# SCH_Syntheseproject_proof_of_concept_com.net
KiCad netlist of a schematic drawn in EasyEDA
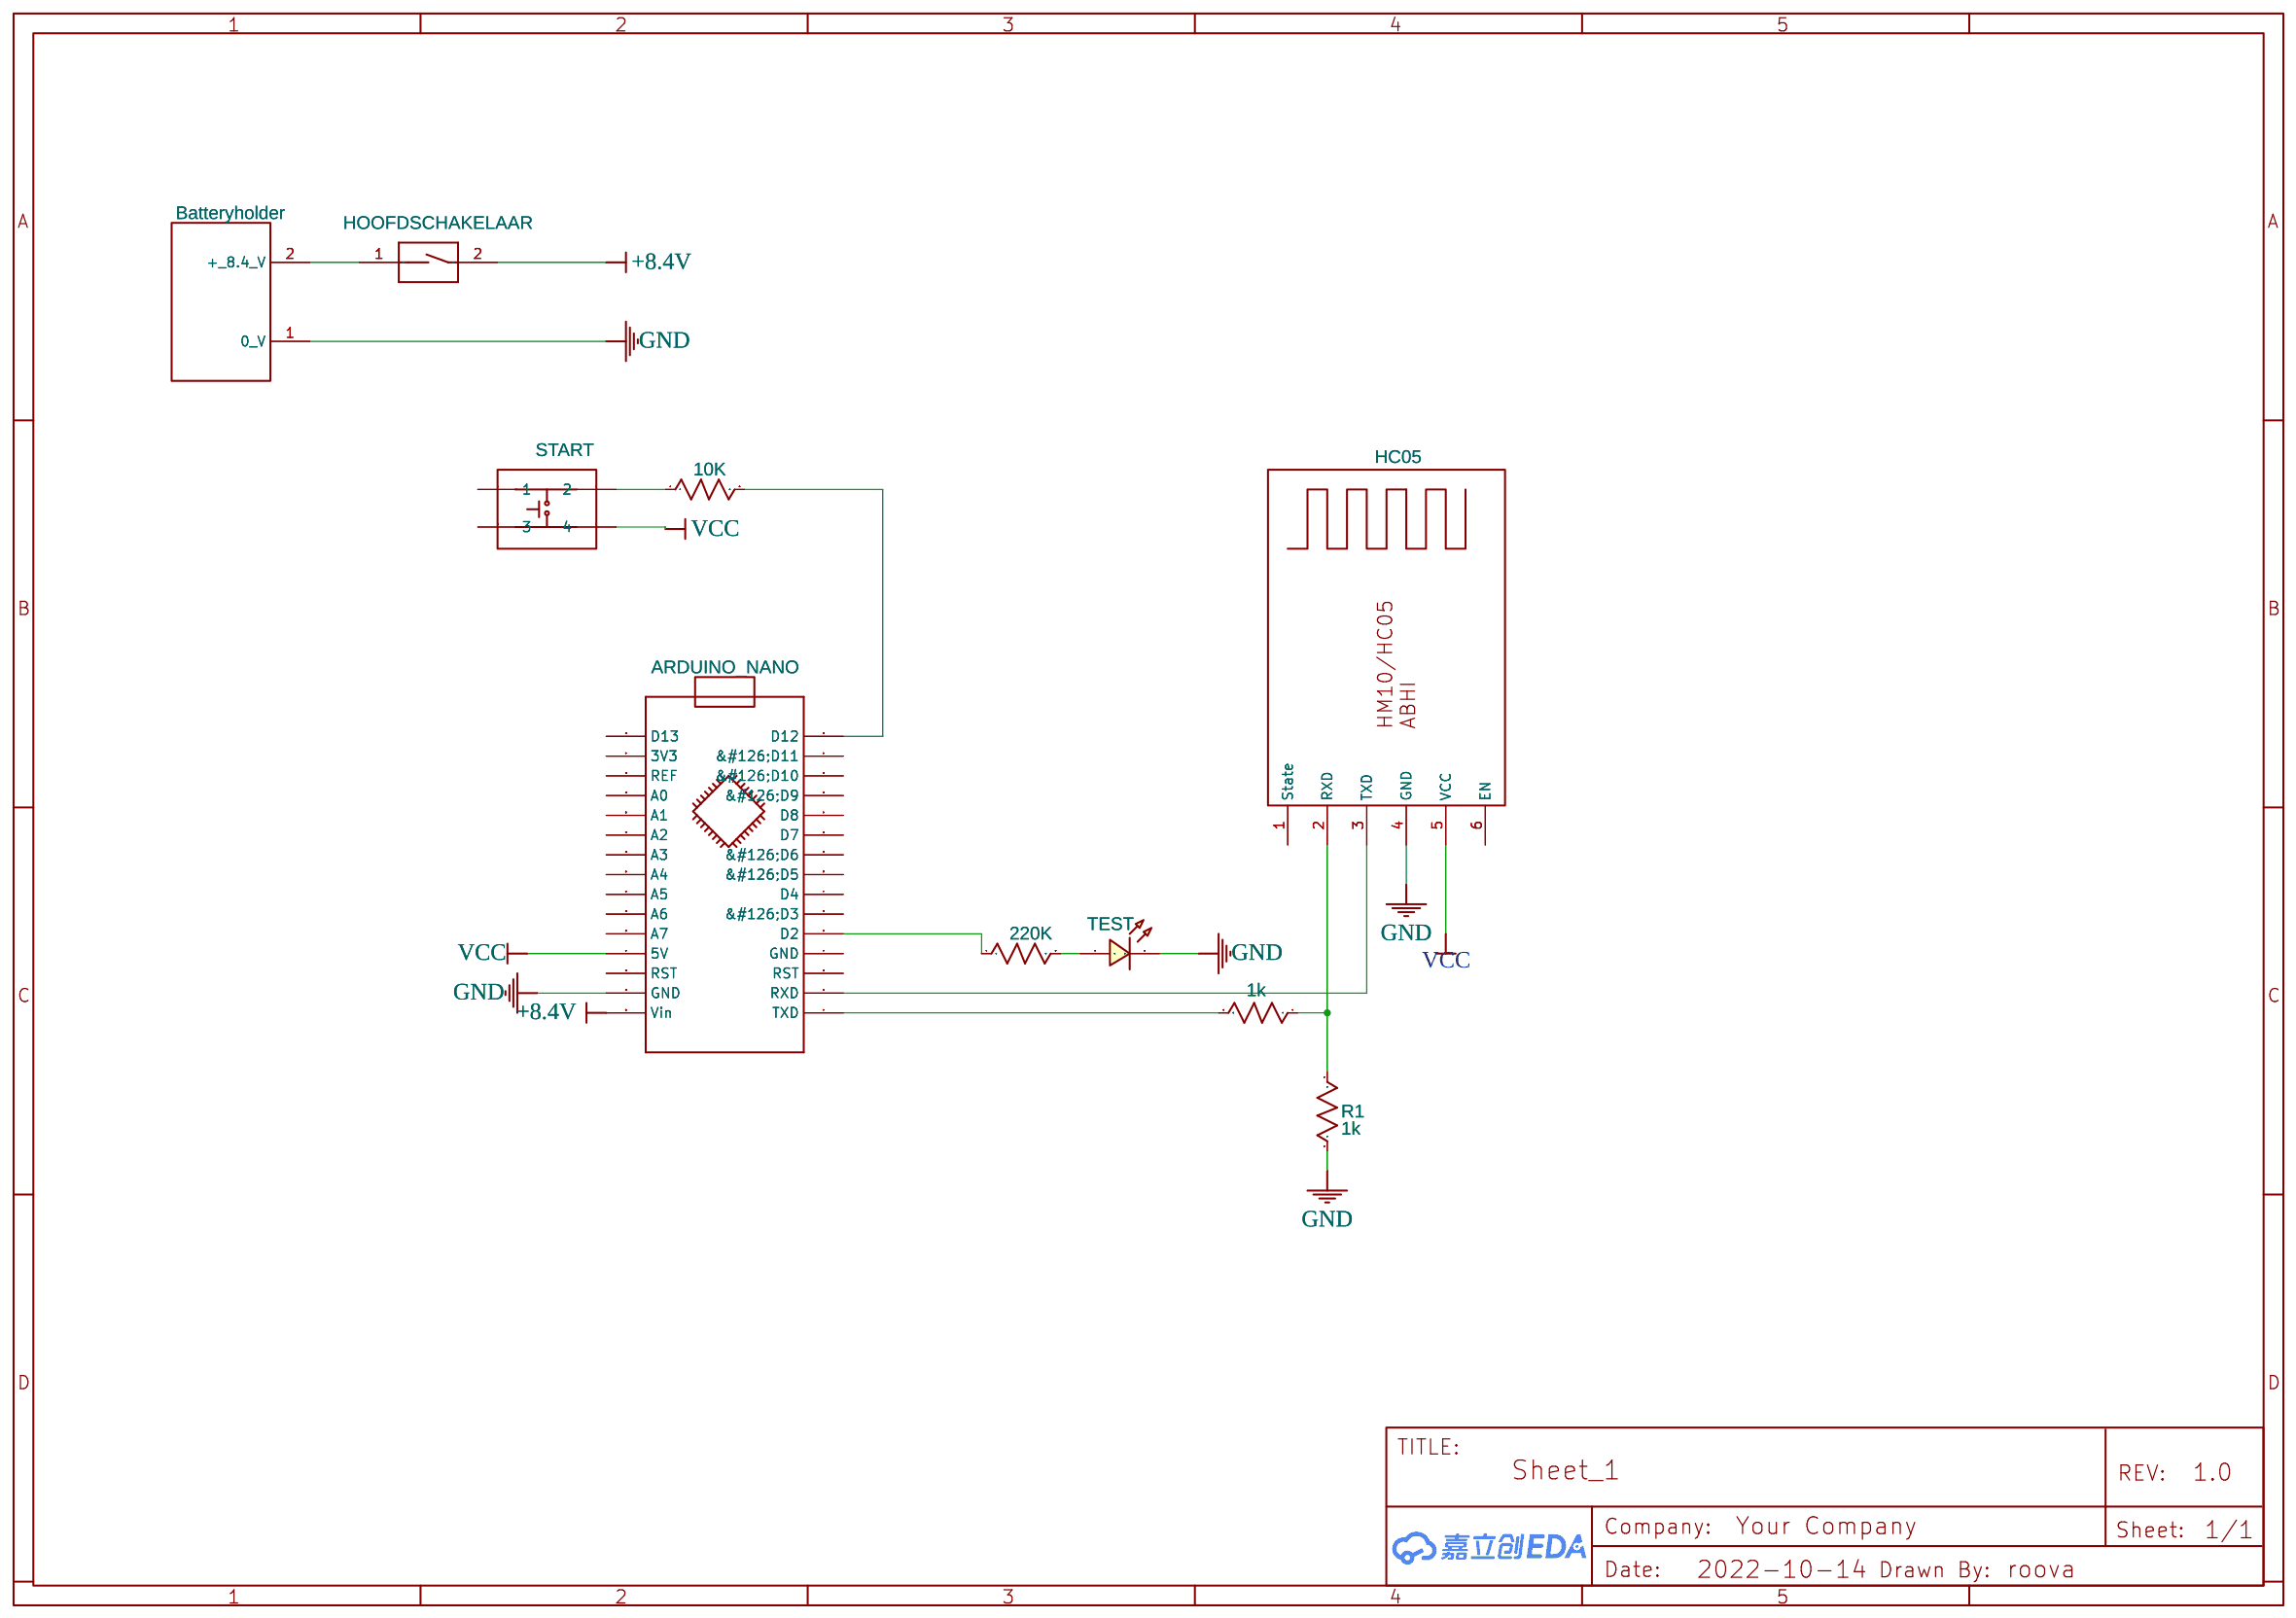
[diagram p0: schematic sheet]

(export (version "E")
  (design (tool "Eeschema 10.0.6"))
  (components
    (comp (ref "10K") (value "1k") (libsource (lib "") (part "R_0603_US_1")))
    (comp (ref "220K") (value "1k") (libsource (lib "") (part "R_0603_US")))
    (comp (ref "ARDUINO_NANO")
      (value "ARDUINO-NANO_V3")
      (fields (field (name "BOM_Manufacturer Part") "ARDUINO-NANO_AK"))
      (libsource (lib "") (part "ARDUINO-NANO_V3"))
    )
    (comp (ref "HOOFDSCHAKELAAR")
      (value "DIP1")
      (fields
        (field (name "BOM_Manufacturer Part") "A6TN-1101")
        (field (name "BOM_Supplier Part") "Z12167-ND")
      )
      (libsource (lib "") (part "DIP1"))
    )
    (comp (ref "R1") (value "1k") (libsource (lib "") (part "R_0603_US_2")))
    (comp (ref "R2") (value "1k") (libsource (lib "") (part "R_0603_US_3")))
    (comp (ref "START")
      (value "PUSHBUTTON 6X6X4.5 4 PINS COPY")
      (fields (field (name "BOM_Manufacturer Part") "sparkfun"))
      (libsource (lib "") (part "PUSHBUTTON 6X6X4.5 4 PINS COPY"))
    )
    (comp (ref "TEST")
      (value "LED-0603_R")
      (fields
        (field (name "BOM_Manufacturer Part") "19-217/R6C-AL1M2VY/3T")
        (field (name "BOM_Supplier Part") "C72044")
      )
      (libsource (lib "") (part "LED-0603_R"))
    )
    (comp (ref "U3") (value "HC05") (libsource (lib "") (part "HC05/HM10-Abhi")))
    (comp (ref "U4") (value "Batteryholder") (libsource (lib "") (part "Batteryholder")))
  )
  (nets
    (net (code "1") (name "+8.4V") (class "Default")
      (node (ref "ARDUINO_NANO") (pin "30") (pinfunction "Vin_30") (pintype "unspecified"))
      (node (ref "HOOFDSCHAKELAAR") (pin "2") (pinfunction "2_2") (pintype "unspecified"))
    )
    (net (code "2") (name "GND") (class "Default")
      (node (ref "ARDUINO_NANO") (pin "29") (pinfunction "GND_29") (pintype "unspecified"))
      (node (ref "R1") (pin "1") (pinfunction "1_1") (pintype "unspecified"))
      (node (ref "TEST") (pin "2") (pinfunction "2_2") (pintype "unspecified"))
      (node (ref "U3") (pin "4") (pinfunction "GND_4") (pintype "unspecified"))
      (node (ref "U4") (pin "1") (pinfunction "0_V_1") (pintype "unspecified"))
    )
    (net (code "3") (name "Net-(10K-Pad1)") (class "Default")
      (node (ref "10K") (pin "1") (pinfunction "1_1") (pintype "unspecified"))
      (node (ref "START") (pin "2") (pinfunction "2_2") (pintype "unspecified"))
    )
    (net (code "4") (name "Net-(220K-Pad2)") (class "Default")
      (node (ref "220K") (pin "2") (pinfunction "2_2") (pintype "unspecified"))
      (node (ref "TEST") (pin "1") (pinfunction "1_1") (pintype "unspecified"))
    )
    (net (code "5") (name "Net-(ARDUINO_NANO-D2)") (class "Default")
      (node (ref "220K") (pin "1") (pinfunction "1_1") (pintype "unspecified"))
      (node (ref "ARDUINO_NANO") (pin "5") (pinfunction "D2_5") (pintype "unspecified"))
    )
    (net (code "6") (name "Net-(ARDUINO_NANO-D12)") (class "Default")
      (node (ref "10K") (pin "2") (pinfunction "2_2") (pintype "unspecified"))
      (node (ref "ARDUINO_NANO") (pin "15") (pinfunction "D12_15") (pintype "unspecified"))
    )
    (net (code "7") (name "Net-(ARDUINO_NANO-RXD)") (class "Default")
      (node (ref "ARDUINO_NANO") (pin "2") (pinfunction "RXD_2") (pintype "unspecified"))
      (node (ref "U3") (pin "3") (pinfunction "TXD_3") (pintype "unspecified"))
    )
    (net (code "8") (name "Net-(ARDUINO_NANO-TXD)") (class "Default")
      (node (ref "ARDUINO_NANO") (pin "1") (pinfunction "TXD_1") (pintype "unspecified"))
      (node (ref "R2") (pin "2") (pinfunction "2_2") (pintype "unspecified"))
    )
    (net (code "9") (name "Net-(U3-RXD)") (class "Default")
      (node (ref "R1") (pin "2") (pinfunction "2_2") (pintype "unspecified"))
      (node (ref "R2") (pin "1") (pinfunction "1_1") (pintype "unspecified"))
      (node (ref "U3") (pin "2") (pinfunction "RXD_2") (pintype "unspecified"))
    )
    (net (code "10") (name "Net-(U4-+_8.4_V)") (class "Default")
      (node (ref "HOOFDSCHAKELAAR") (pin "1") (pinfunction "1_1") (pintype "unspecified"))
      (node (ref "U4") (pin "2") (pinfunction "+_8.4_V_2") (pintype "unspecified"))
    )
    (net (code "11") (name "VCC") (class "Default")
      (node (ref "ARDUINO_NANO") (pin "27") (pinfunction "5V_27") (pintype "unspecified"))
      (node (ref "START") (pin "4") (pinfunction "4_4") (pintype "unspecified"))
      (node (ref "U3") (pin "5") (pinfunction "VCC_5") (pintype "unspecified"))
    )
    (net (code "12") (name "unconnected-(ARDUINO_NANO-&#126;D3-Pad6)") (class "Default")
      (node (ref "ARDUINO_NANO") (pin "6") (pinfunction "&#126;D3_6") (pintype "unspecified"))
    )
    (net (code "13") (name "unconnected-(ARDUINO_NANO-&#126;D5-Pad8)") (class "Default")
      (node (ref "ARDUINO_NANO") (pin "8") (pinfunction "&#126;D5_8") (pintype "unspecified"))
    )
    (net (code "14") (name "unconnected-(ARDUINO_NANO-&#126;D6-Pad9)") (class "Default")
      (node (ref "ARDUINO_NANO") (pin "9") (pinfunction "&#126;D6_9") (pintype "unspecified"))
    )
    (net (code "15") (name "unconnected-(ARDUINO_NANO-&#126;D9-Pad12)") (class "Default")
      (node (ref "ARDUINO_NANO") (pin "12") (pinfunction "&#126;D9_12") (pintype "unspecified"))
    )
    (net (code "16") (name "unconnected-(ARDUINO_NANO-&#126;D10-Pad13)") (class "Default")
      (node (ref "ARDUINO_NANO") (pin "13") (pinfunction "&#126;D10_13") (pintype "unspecified"))
    )
    (net (code "17") (name "unconnected-(ARDUINO_NANO-&#126;D11-Pad14)") (class "Default")
      (node (ref "ARDUINO_NANO") (pin "14") (pinfunction "&#126;D11_14") (pintype "unspecified"))
    )
    (net (code "18") (name "unconnected-(ARDUINO_NANO-3V3-Pad17)") (class "Default")
      (node (ref "ARDUINO_NANO") (pin "17") (pinfunction "3V3_17") (pintype "unspecified"))
    )
    (net (code "19") (name "unconnected-(ARDUINO_NANO-A0-Pad19)") (class "Default")
      (node (ref "ARDUINO_NANO") (pin "19") (pinfunction "A0_19") (pintype "unspecified"))
    )
    (net (code "20") (name "unconnected-(ARDUINO_NANO-A1-Pad20)") (class "Default")
      (node (ref "ARDUINO_NANO") (pin "20") (pinfunction "A1_20") (pintype "unspecified"))
    )
    (net (code "21") (name "unconnected-(ARDUINO_NANO-A2-Pad21)") (class "Default")
      (node (ref "ARDUINO_NANO") (pin "21") (pinfunction "A2_21") (pintype "unspecified"))
    )
    (net (code "22") (name "unconnected-(ARDUINO_NANO-A3-Pad22)") (class "Default")
      (node (ref "ARDUINO_NANO") (pin "22") (pinfunction "A3_22") (pintype "unspecified"))
    )
    (net (code "23") (name "unconnected-(ARDUINO_NANO-A4-Pad23)") (class "Default")
      (node (ref "ARDUINO_NANO") (pin "23") (pinfunction "A4_23") (pintype "unspecified"))
    )
    (net (code "24") (name "unconnected-(ARDUINO_NANO-A5-Pad24)") (class "Default")
      (node (ref "ARDUINO_NANO") (pin "24") (pinfunction "A5_24") (pintype "unspecified"))
    )
    (net (code "25") (name "unconnected-(ARDUINO_NANO-A6-Pad25)") (class "Default")
      (node (ref "ARDUINO_NANO") (pin "25") (pinfunction "A6_25") (pintype "unspecified"))
    )
    (net (code "26") (name "unconnected-(ARDUINO_NANO-A7-Pad26)") (class "Default")
      (node (ref "ARDUINO_NANO") (pin "26") (pinfunction "A7_26") (pintype "unspecified"))
    )
    (net (code "27") (name "unconnected-(ARDUINO_NANO-D4-Pad7)") (class "Default")
      (node (ref "ARDUINO_NANO") (pin "7") (pinfunction "D4_7") (pintype "unspecified"))
    )
    (net (code "28") (name "unconnected-(ARDUINO_NANO-D7-Pad10)") (class "Default")
      (node (ref "ARDUINO_NANO") (pin "10") (pinfunction "D7_10") (pintype "unspecified"))
    )
    (net (code "29") (name "unconnected-(ARDUINO_NANO-D8-Pad11)") (class "Default")
      (node (ref "ARDUINO_NANO") (pin "11") (pinfunction "D8_11") (pintype "unspecified"))
    )
    (net (code "30") (name "unconnected-(ARDUINO_NANO-D13-Pad16)") (class "Default")
      (node (ref "ARDUINO_NANO") (pin "16") (pinfunction "D13_16") (pintype "unspecified"))
    )
    (net (code "31") (name "unconnected-(ARDUINO_NANO-GND-Pad4)") (class "Default")
      (node (ref "ARDUINO_NANO") (pin "4") (pinfunction "GND_4") (pintype "unspecified"))
    )
    (net (code "32") (name "unconnected-(ARDUINO_NANO-REF-Pad18)") (class "Default")
      (node (ref "ARDUINO_NANO") (pin "18") (pinfunction "REF_18") (pintype "unspecified"))
    )
    (net (code "33") (name "unconnected-(ARDUINO_NANO-RST-Pad3)") (class "Default")
      (node (ref "ARDUINO_NANO") (pin "3") (pinfunction "RST_3") (pintype "unspecified"))
    )
    (net (code "34") (name "unconnected-(ARDUINO_NANO-RST-Pad28)") (class "Default")
      (node (ref "ARDUINO_NANO") (pin "28") (pinfunction "RST_28") (pintype "unspecified"))
    )
    (net (code "35") (name "unconnected-(START-Pad1)") (class "Default")
      (node (ref "START") (pin "1") (pinfunction "1_1") (pintype "unspecified"))
    )
    (net (code "36") (name "unconnected-(START-Pad3)") (class "Default")
      (node (ref "START") (pin "3") (pinfunction "3_3") (pintype "unspecified"))
    )
    (net (code "37") (name "unconnected-(U3-EN-Pad6)") (class "Default")
      (node (ref "U3") (pin "6") (pinfunction "EN_6") (pintype "unspecified"))
    )
    (net (code "38") (name "unconnected-(U3-State-Pad1)") (class "Default")
      (node (ref "U3") (pin "1") (pinfunction "State_1") (pintype "unspecified"))
    )
  )
)
